# 2_Port_Memory.net
KiCad netlist of a schematic drawn in EAGLE
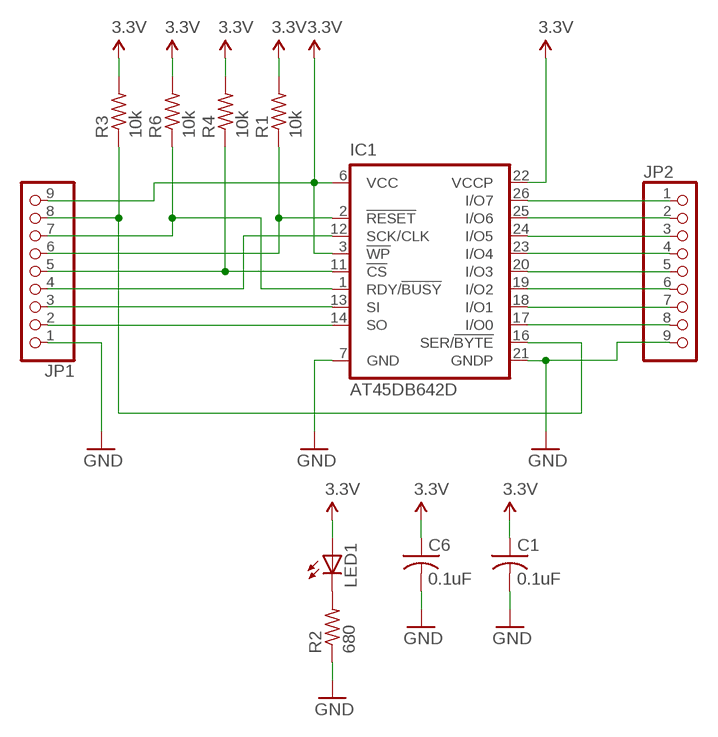
[diagram p0: schematic, sheet 1]

(export (version "E")
  (design (tool "Eeschema 10.0.6"))
  (components
    (comp (ref "C1")
      (value "0.1uF")
      (footprint "eagle-import:0603_RESISTOR")
      (libsource (lib "eagle-import") (part "0603_CAP"))
    )
    (comp (ref "C6")
      (value "0.1uF")
      (footprint "eagle-import:0603_RESISTOR")
      (libsource (lib "eagle-import") (part "0603_CAP"))
    )
    (comp (ref "IC1")
      (value "AT45DB642D")
      (footprint "eagle-import:28T-TSOP-1")
      (fields (field (name "MPN") "AT45DB642D-TU"))
      (libsource (lib "eagle-import") (part "AT45DB642D"))
    )
    (comp (ref "JP1")
      (value "PINHD-1X9")
      (footprint "eagle-import:1X09")
      (libsource (lib "eagle-import") (part "PINHD-1X9"))
    )
    (comp (ref "JP2")
      (value "PINHD-1X9")
      (footprint "eagle-import:1X09")
      (libsource (lib "eagle-import") (part "PINHD-1X9"))
    )
    (comp (ref "LED1")
      (value "LEDCHIP-LED0603")
      (footprint "eagle-import:CHIP-LED0603")
      (libsource (lib "eagle-import") (part "LEDCHIP-LED0603"))
    )
    (comp (ref "R1")
      (value "10k")
      (footprint "eagle-import:0603_RESISTOR")
      (libsource (lib "eagle-import") (part "0603_RESISTOR"))
    )
    (comp (ref "R2")
      (value "680")
      (footprint "eagle-import:0603_RESISTOR")
      (libsource (lib "eagle-import") (part "0603_RESISTOR"))
    )
    (comp (ref "R3")
      (value "10k")
      (footprint "eagle-import:0603_RESISTOR")
      (libsource (lib "eagle-import") (part "0603_RESISTOR"))
    )
    (comp (ref "R4")
      (value "10k")
      (footprint "eagle-import:0603_RESISTOR")
      (libsource (lib "eagle-import") (part "0603_RESISTOR"))
    )
    (comp (ref "R6")
      (value "10k")
      (footprint "eagle-import:0603_RESISTOR")
      (libsource (lib "eagle-import") (part "0603_RESISTOR"))
    )
  )
  (nets
    (net (code "1") (name "3.3V") (class "Default")
      (node (ref "C1") (pin "1") (pinfunction "1_1") (pintype "passive"))
      (node (ref "C6") (pin "1") (pinfunction "1_1") (pintype "passive"))
      (node (ref "IC1") (pin "22") (pinfunction "VCCP_22") (pintype "power_in"))
      (node (ref "IC1") (pin "3") (pinfunction "~{WP}_3") (pintype "input"))
      (node (ref "IC1") (pin "6") (pinfunction "VCC_6") (pintype "power_in"))
      (node (ref "JP1") (pin "9") (pinfunction "9_9") (pintype "passive"))
      (node (ref "LED1") (pin "A") (pinfunction "A_A") (pintype "passive"))
      (node (ref "R1") (pin "2") (pinfunction "2_2") (pintype "passive"))
      (node (ref "R3") (pin "2") (pinfunction "2_2") (pintype "passive"))
      (node (ref "R4") (pin "2") (pinfunction "2_2") (pintype "passive"))
      (node (ref "R6") (pin "2") (pinfunction "2_2") (pintype "passive"))
    )
    (net (code "2") (name "GND") (class "Default")
      (node (ref "C1") (pin "2") (pinfunction "2_2") (pintype "passive"))
      (node (ref "C6") (pin "2") (pinfunction "2_2") (pintype "passive"))
      (node (ref "IC1") (pin "21") (pinfunction "GNDP_21") (pintype "power_in"))
      (node (ref "IC1") (pin "7") (pinfunction "GND_7") (pintype "power_in"))
      (node (ref "JP1") (pin "1") (pinfunction "1_1") (pintype "passive"))
      (node (ref "JP2") (pin "9") (pinfunction "9_9") (pintype "passive"))
      (node (ref "R2") (pin "1") (pinfunction "1_1") (pintype "passive"))
    )
    (net (code "3") (name "Net-(IC1-I{slash}O0)") (class "Default")
      (node (ref "IC1") (pin "17") (pinfunction "I/O0_17") (pintype "bidirectional"))
      (node (ref "JP2") (pin "8") (pinfunction "8_8") (pintype "passive"))
    )
    (net (code "4") (name "Net-(IC1-I{slash}O1)") (class "Default")
      (node (ref "IC1") (pin "18") (pinfunction "I/O1_18") (pintype "bidirectional"))
      (node (ref "JP2") (pin "7") (pinfunction "7_7") (pintype "passive"))
    )
    (net (code "5") (name "Net-(IC1-I{slash}O2)") (class "Default")
      (node (ref "IC1") (pin "19") (pinfunction "I/O2_19") (pintype "bidirectional"))
      (node (ref "JP2") (pin "6") (pinfunction "6_6") (pintype "passive"))
    )
    (net (code "6") (name "Net-(IC1-I{slash}O3)") (class "Default")
      (node (ref "IC1") (pin "20") (pinfunction "I/O3_20") (pintype "bidirectional"))
      (node (ref "JP2") (pin "5") (pinfunction "5_5") (pintype "passive"))
    )
    (net (code "7") (name "Net-(IC1-I{slash}O4)") (class "Default")
      (node (ref "IC1") (pin "23") (pinfunction "I/O4_23") (pintype "bidirectional"))
      (node (ref "JP2") (pin "4") (pinfunction "4_4") (pintype "passive"))
    )
    (net (code "8") (name "Net-(IC1-I{slash}O5)") (class "Default")
      (node (ref "IC1") (pin "24") (pinfunction "I/O5_24") (pintype "bidirectional"))
      (node (ref "JP2") (pin "3") (pinfunction "3_3") (pintype "passive"))
    )
    (net (code "9") (name "Net-(IC1-I{slash}O6)") (class "Default")
      (node (ref "IC1") (pin "25") (pinfunction "I/O6_25") (pintype "bidirectional"))
      (node (ref "JP2") (pin "2") (pinfunction "2_2") (pintype "passive"))
    )
    (net (code "10") (name "Net-(IC1-I{slash}O7)") (class "Default")
      (node (ref "IC1") (pin "26") (pinfunction "I/O7_26") (pintype "bidirectional"))
      (node (ref "JP2") (pin "1") (pinfunction "1_1") (pintype "passive"))
    )
    (net (code "11") (name "Net-(IC1-RDY{slash}~{BUSY})") (class "Default")
      (node (ref "IC1") (pin "1") (pinfunction "RDY/~{BUSY}_1") (pintype "output"))
      (node (ref "JP1") (pin "7") (pinfunction "7_7") (pintype "passive"))
      (node (ref "R6") (pin "1") (pinfunction "1_1") (pintype "passive"))
    )
    (net (code "12") (name "Net-(IC1-SCK{slash}CLK)") (class "Default")
      (node (ref "IC1") (pin "12") (pinfunction "SCK/CLK_12") (pintype "input"))
      (node (ref "JP1") (pin "4") (pinfunction "4_4") (pintype "passive"))
    )
    (net (code "13") (name "Net-(IC1-SER{slash}~{BYTE})") (class "Default")
      (node (ref "IC1") (pin "16") (pinfunction "SER/~{BYTE}_16") (pintype "input"))
      (node (ref "JP1") (pin "8") (pinfunction "8_8") (pintype "passive"))
      (node (ref "R3") (pin "1") (pinfunction "1_1") (pintype "passive"))
    )
    (net (code "14") (name "Net-(IC1-SI)") (class "Default")
      (node (ref "IC1") (pin "13") (pinfunction "SI_13") (pintype "input"))
      (node (ref "JP1") (pin "3") (pinfunction "3_3") (pintype "passive"))
    )
    (net (code "15") (name "Net-(IC1-SO)") (class "Default")
      (node (ref "IC1") (pin "14") (pinfunction "SO_14") (pintype "output"))
      (node (ref "JP1") (pin "2") (pinfunction "2_2") (pintype "passive"))
    )
    (net (code "16") (name "Net-(IC1-~{CS})") (class "Default")
      (node (ref "IC1") (pin "11") (pinfunction "~{CS}_11") (pintype "input"))
      (node (ref "JP1") (pin "5") (pinfunction "5_5") (pintype "passive"))
      (node (ref "R4") (pin "1") (pinfunction "1_1") (pintype "passive"))
    )
    (net (code "17") (name "Net-(IC1-~{RESET})") (class "Default")
      (node (ref "IC1") (pin "2") (pinfunction "~{RESET}_2") (pintype "input"))
      (node (ref "JP1") (pin "6") (pinfunction "6_6") (pintype "passive"))
      (node (ref "R1") (pin "1") (pinfunction "1_1") (pintype "passive"))
    )
    (net (code "18") (name "Net-(LED1-PadC)") (class "Default")
      (node (ref "LED1") (pin "C") (pinfunction "C_C") (pintype "passive"))
      (node (ref "R2") (pin "2") (pinfunction "2_2") (pintype "passive"))
    )
  )
)
